# pidplate-mk-2.net
KiCad netlist of a schematic drawn in EAGLE
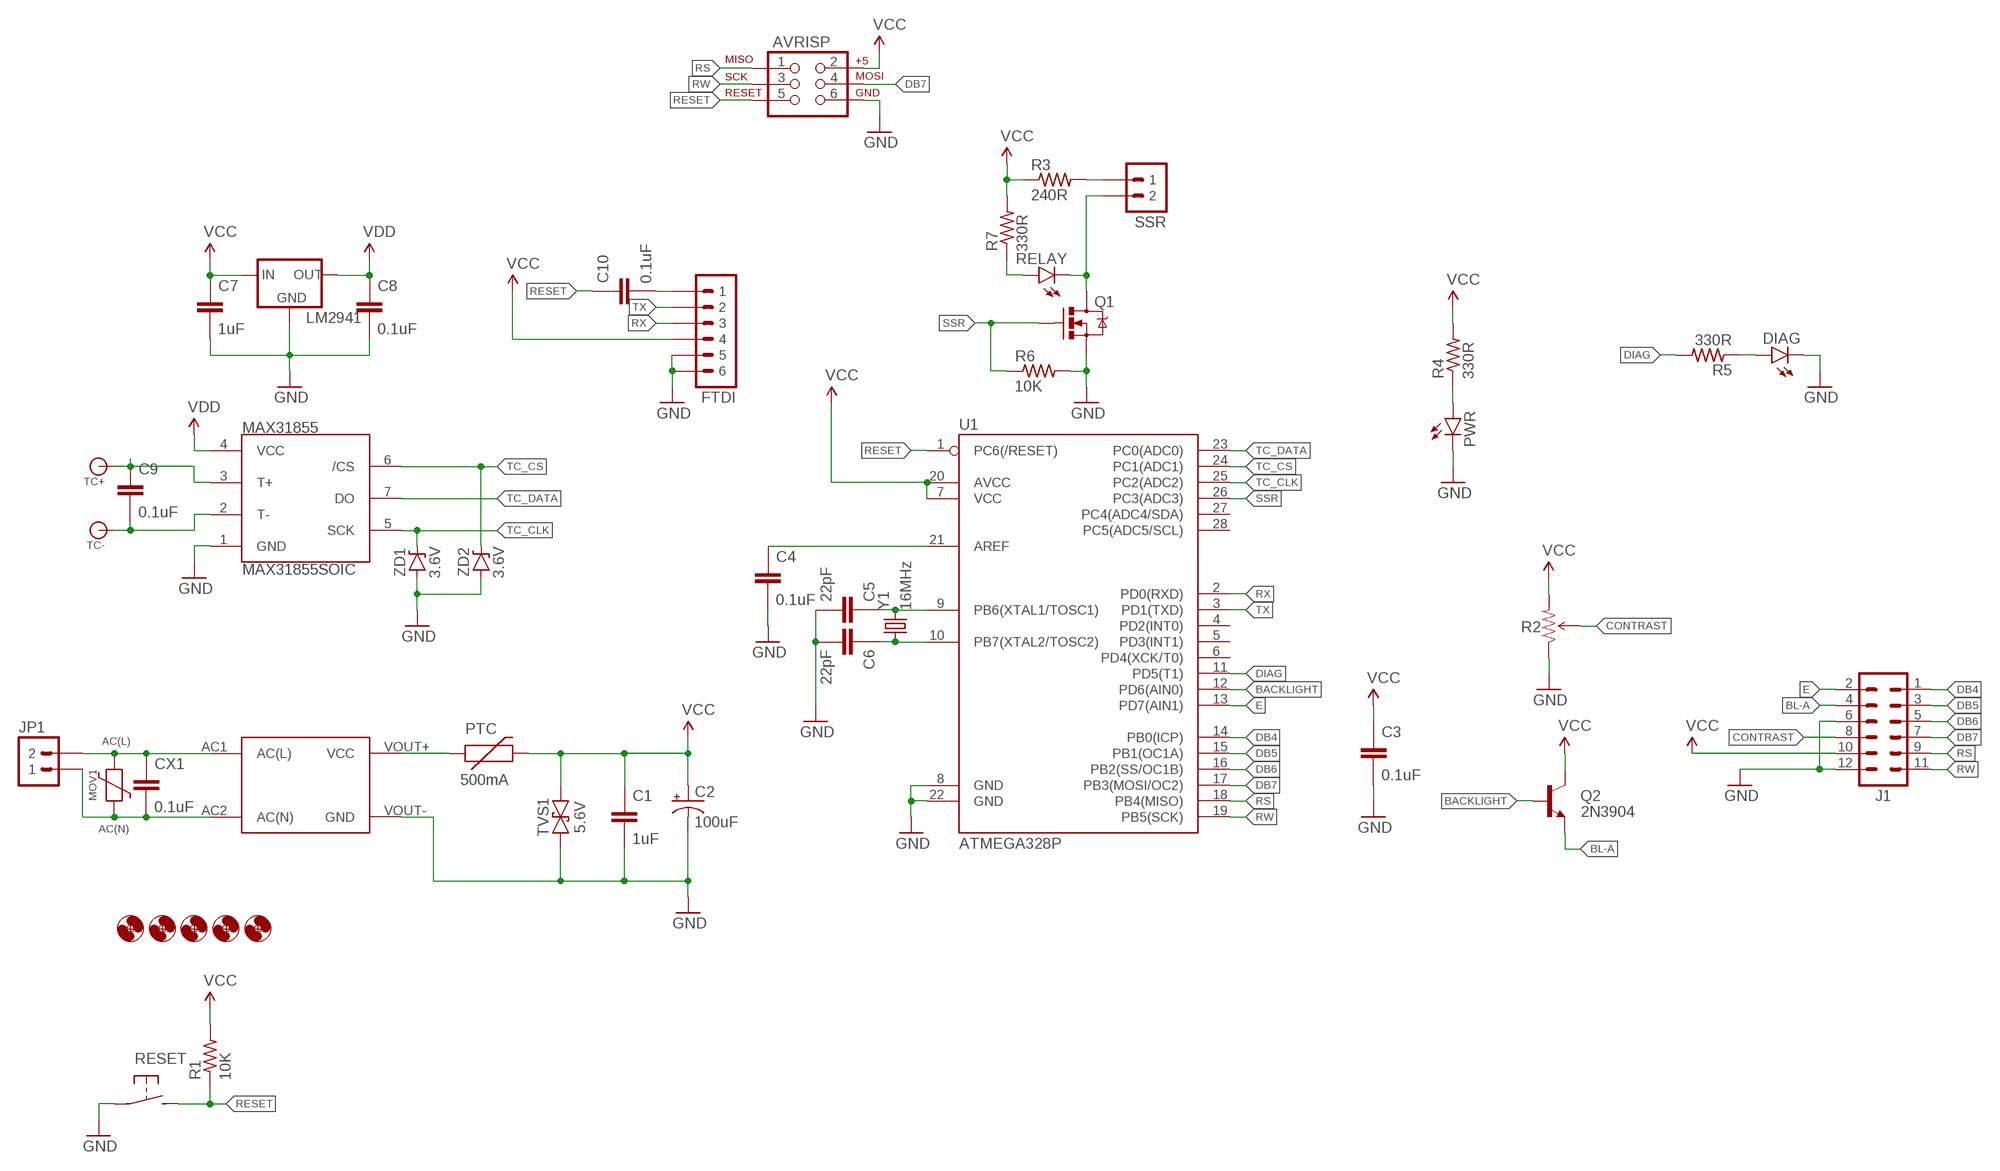
[diagram p0: schematic, sheet 1]

(export (version "E")
  (design (tool "Eeschema 10.0.6"))
  (components
    (comp (ref "AVRISP")
      (value "AVR_SPI_PRG_6PTH")
      (footprint "eagle-import:2X3")
      (libsource (lib "eagle-import") (part "AVR_SPI_PRG_6PTH"))
    )
    (comp (ref "C1")
      (value "1uF")
      (footprint "eagle-import:C025-024X044")
      (libsource (lib "eagle-import") (part "CAPACITOR-CERAMIC025-024X044"))
    )
    (comp (ref "C2")
      (value "100uF")
      (footprint "eagle-import:E2,5-7")
      (libsource (lib "eagle-import") (part "CAPACITOR-POLARIZEDE2.5-7"))
    )
    (comp (ref "C3")
      (value "0.1uF")
      (footprint "eagle-import:C025-024X044")
      (libsource (lib "eagle-import") (part "CAPACITOR-CERAMIC025-024X044"))
    )
    (comp (ref "C4")
      (value "0.1uF")
      (footprint "eagle-import:C025-024X044")
      (libsource (lib "eagle-import") (part "CAPACITOR-CERAMIC025-024X044"))
    )
    (comp (ref "C5")
      (value "22pF")
      (footprint "eagle-import:C025-024X044")
      (libsource (lib "eagle-import") (part "CAPACITOR-CERAMIC025-024X044"))
    )
    (comp (ref "C6")
      (value "22pF")
      (footprint "eagle-import:C025-024X044")
      (libsource (lib "eagle-import") (part "CAPACITOR-CERAMIC025-024X044"))
    )
    (comp (ref "C7")
      (value "1uF")
      (footprint "eagle-import:C025-024X044")
      (libsource (lib "eagle-import") (part "CAPACITOR-CERAMIC025-024X044"))
    )
    (comp (ref "C8")
      (value "0.1uF")
      (footprint "eagle-import:C025-024X044")
      (libsource (lib "eagle-import") (part "CAPACITOR-CERAMIC025-024X044"))
    )
    (comp (ref "C9")
      (value "0.1uF")
      (footprint "eagle-import:C025-024X044")
      (libsource (lib "eagle-import") (part "CAPACITOR-CERAMIC025-024X044"))
    )
    (comp (ref "C10")
      (value "0.1uF")
      (footprint "eagle-import:C025-024X044")
      (libsource (lib "eagle-import") (part "CAPACITOR-CERAMIC025-024X044"))
    )
    (comp (ref "CX1")
      (value "0.1uF")
      (footprint "eagle-import:XC10B5")
      (libsource (lib "eagle-import") (part "CXXC10B5"))
    )
    (comp (ref "DIAG")
      (value "LED3MM")
      (footprint "eagle-import:LED3MM")
      (libsource (lib "eagle-import") (part "LED3MM"))
    )
    (comp (ref "FTDI")
      (value "M06SIP")
      (footprint "eagle-import:1X06")
      (libsource (lib "eagle-import") (part "M06SIP"))
    )
    (comp (ref "H1")
      (value "HOLE#2")
      (footprint "eagle-import:HOLE-#2")
      (libsource (lib "eagle-import") (part "HOLE#2"))
    )
    (comp (ref "H2")
      (value "HOLE#2")
      (footprint "eagle-import:HOLE-#2")
      (libsource (lib "eagle-import") (part "HOLE#2"))
    )
    (comp (ref "H3")
      (value "HOLE#2")
      (footprint "eagle-import:HOLE-#2")
      (libsource (lib "eagle-import") (part "HOLE#2"))
    )
    (comp (ref "H4")
      (value "HOLE#2")
      (footprint "eagle-import:HOLE-#2")
      (libsource (lib "eagle-import") (part "HOLE#2"))
    )
    (comp (ref "H5")
      (value "HOLE#2")
      (footprint "eagle-import:HOLE-#2")
      (libsource (lib "eagle-import") (part "HOLE#2"))
    )
    (comp (ref "J1")
      (value "M06X2PTH")
      (footprint "eagle-import:2X6_PTH")
      (libsource (lib "eagle-import") (part "M06X2PTH"))
    )
    (comp (ref "JP1")
      (value "M023.5MM")
      (footprint "eagle-import:SCREWTERMINAL-3.5MM-2")
      (libsource (lib "eagle-import") (part "M023.5MM"))
    )
    (comp (ref "LM2941")
      (value "L2941")
      (footprint "eagle-import:TO-92-AMMO")
      (libsource (lib "eagle-import") (part "V_REG_78XXTO-92-INLINE"))
    )
    (comp (ref "MAX31855")
      (value "MAX31855SOIC")
      (footprint "eagle-import:SOIC127P600X175-8N")
      (libsource (lib "eagle-import") (part "MAX31855SOIC"))
    )
    (comp (ref "MOV1")
      (value "VARISITORVAR-5.08MM-PTH")
      (footprint "eagle-import:VAR-5.08MM-PTH")
      (libsource (lib "eagle-import") (part "VARISITORVAR-5.08MM-PTH"))
    )
    (comp (ref "PTC")
      (value "500mA")
      (footprint "eagle-import:PTC")
      (libsource (lib "eagle-import") (part "PTCPTH"))
    )
    (comp (ref "PWR")
      (value "LED3MM")
      (footprint "eagle-import:LED3MM")
      (libsource (lib "eagle-import") (part "LED3MM"))
    )
    (comp (ref "Q1")
      (value "2N7000")
      (footprint "eagle-import:TO-92-AMMO")
      (libsource (lib "eagle-import") (part "MOSFET-NCHANNEL2N7000-AMMO"))
    )
    (comp (ref "Q2")
      (value "2N3904")
      (footprint "eagle-import:TO-92-AMMO")
      (libsource (lib "eagle-import") (part "TRANSISTOR_NPNTO-92-AMMO-CBE"))
    )
    (comp (ref "R1")
      (value "10K")
      (footprint "eagle-import:RESISTOR-AXIAL-PTH-5.08MM")
      (libsource (lib "eagle-import") (part "RESISTORPTH-AXIAL-5.08MM"))
    )
    (comp (ref "R2")
      (value "20K")
      (footprint "eagle-import:TRIM_POT_PTH")
      (libsource (lib "eagle-import") (part "TRIMPOTPTH"))
    )
    (comp (ref "R3")
      (value "240R")
      (footprint "eagle-import:RESISTOR-AXIAL-PTH-6.35MM")
      (libsource (lib "eagle-import") (part "RESISTORPTH-AXIAL-6.35MM"))
    )
    (comp (ref "R4")
      (value "330R")
      (footprint "eagle-import:RESISTOR-AXIAL-PTH-5.08MM")
      (libsource (lib "eagle-import") (part "RESISTORPTH-AXIAL-5.08MM"))
    )
    (comp (ref "R5")
      (value "330R")
      (footprint "eagle-import:RESISTOR-AXIAL-PTH-5.08MM")
      (libsource (lib "eagle-import") (part "RESISTORPTH-AXIAL-5.08MM"))
    )
    (comp (ref "R6")
      (value "10K")
      (footprint "eagle-import:RESISTOR-AXIAL-PTH-6.35MM")
      (libsource (lib "eagle-import") (part "RESISTORPTH-AXIAL-6.35MM"))
    )
    (comp (ref "R7")
      (value "330R")
      (footprint "eagle-import:RESISTOR-AXIAL-PTH-5.08MM")
      (libsource (lib "eagle-import") (part "RESISTORPTH-AXIAL-5.08MM"))
    )
    (comp (ref "RELAY")
      (value "LED3MM")
      (footprint "eagle-import:LED3MM")
      (libsource (lib "eagle-import") (part "LED3MM"))
    )
    (comp (ref "RESET")
      (value "SPST-NO-TACT3MM-RA")
      (footprint "eagle-import:TACTILE-PTH-SIDE")
      (libsource (lib "eagle-import") (part "SPST-NO-TACT3MM-RA"))
    )
    (comp (ref "SSR")
      (value "M02JST-PTH-VERT")
      (footprint "eagle-import:JST-2-PH-VERT-PTH")
      (libsource (lib "eagle-import") (part "M02JST-PTH-VERT"))
    )
    (comp (ref "TC+")
      (value "BANANA_CONNPTH-RA")
      (footprint "eagle-import:BANANA-PTH-RA-SAFEWORD")
      (libsource (lib "eagle-import") (part "BANANA_CONNPTH-RA"))
    )
    (comp (ref "TC-")
      (value "BANANA_CONNPTH-RA")
      (footprint "eagle-import:BANANA-PTH-RA-SAFEWORD")
      (libsource (lib "eagle-import") (part "BANANA_CONNPTH-RA"))
    )
    (comp (ref "TVS1")
      (value "5.6V")
      (footprint "eagle-import:DO-41-TVS")
      (libsource (lib "eagle-import") (part "TVSDO-41-TVS-BIDIRECTIONAL"))
    )
    (comp (ref "U1")
      (value "ATMEGA328P")
      (footprint "eagle-import:DIL28-3")
      (libsource (lib "eagle-import") (part "ATMEGA328P_PDIP"))
    )
    (comp (ref "U3")
      (value "VSK-S1")
      (footprint "eagle-import:VSK-S1")
      (libsource (lib "eagle-import") (part "VSK-S1"))
    )
    (comp (ref "Y1")
      (value "16MHz")
      (footprint "eagle-import:HC49U-V")
      (libsource (lib "eagle-import") (part "CRYSTALHC49UV"))
    )
    (comp (ref "ZD1")
      (value "3.6V")
      (footprint "eagle-import:DIODE-7.68MM")
      (libsource (lib "eagle-import") (part "DIODE-ZENERPTH-7.68MM"))
    )
    (comp (ref "ZD2")
      (value "3.6V")
      (footprint "eagle-import:DIODE-7.68MM")
      (libsource (lib "eagle-import") (part "DIODE-ZENERPTH-7.68MM"))
    )
  )
  (nets
    (net (code "1") (name "/AC(L)") (class "Default")
      (node (ref "CX1") (pin "1") (pinfunction "1_1") (pintype "passive"))
      (node (ref "JP1") (pin "2") (pinfunction "2_2") (pintype "passive"))
      (node (ref "MOV1") (pin "2") (pinfunction "P$2_2") (pintype "bidirectional"))
      (node (ref "U3") (pin "AC1") (pinfunction "AC(L)_AC1") (pintype "bidirectional"))
    )
    (net (code "2") (name "/AC(N)") (class "Default")
      (node (ref "CX1") (pin "2") (pinfunction "2_2") (pintype "passive"))
      (node (ref "JP1") (pin "1") (pinfunction "1_1") (pintype "passive"))
      (node (ref "MOV1") (pin "1") (pinfunction "P$1_1") (pintype "bidirectional"))
      (node (ref "U3") (pin "AC2") (pinfunction "AC(N)_AC2") (pintype "bidirectional"))
    )
    (net (code "3") (name "BACKLIGHT") (class "Default")
      (node (ref "Q2") (pin "2") (pinfunction "B_2") (pintype "passive"))
      (node (ref "U1") (pin "12") (pinfunction "PD6(AIN0)_12") (pintype "bidirectional"))
    )
    (net (code "4") (name "BL-A") (class "Default")
      (node (ref "J1") (pin "4") (pinfunction "4_4") (pintype "passive"))
      (node (ref "Q2") (pin "3") (pinfunction "E_3") (pintype "passive"))
    )
    (net (code "5") (name "CONTRAST") (class "Default")
      (node (ref "J1") (pin "8") (pinfunction "8_8") (pintype "passive"))
      (node (ref "R2") (pin "2") (pinfunction "WIPER_2") (pintype "passive"))
    )
    (net (code "6") (name "DB4") (class "Default")
      (node (ref "J1") (pin "1") (pinfunction "1_1") (pintype "passive"))
      (node (ref "U1") (pin "14") (pinfunction "PB0(ICP)_14") (pintype "bidirectional"))
    )
    (net (code "7") (name "DB5") (class "Default")
      (node (ref "J1") (pin "3") (pinfunction "3_3") (pintype "passive"))
      (node (ref "U1") (pin "15") (pinfunction "PB1(OC1A)_15") (pintype "bidirectional"))
    )
    (net (code "8") (name "DB6") (class "Default")
      (node (ref "J1") (pin "5") (pinfunction "5_5") (pintype "passive"))
      (node (ref "U1") (pin "16") (pinfunction "PB2(SS/OC1B)_16") (pintype "bidirectional"))
    )
    (net (code "9") (name "DB7") (class "Default")
      (node (ref "AVRISP") (pin "4") (pinfunction "4_4") (pintype "passive"))
      (node (ref "J1") (pin "7") (pinfunction "7_7") (pintype "passive"))
      (node (ref "U1") (pin "17") (pinfunction "PB3(MOSI/OC2)_17") (pintype "bidirectional"))
    )
    (net (code "10") (name "DIAG") (class "Default")
      (node (ref "R5") (pin "P$2") (pinfunction "2_P$2") (pintype "passive"))
      (node (ref "U1") (pin "11") (pinfunction "PD5(T1)_11") (pintype "bidirectional"))
    )
    (net (code "11") (name "E") (class "Default")
      (node (ref "J1") (pin "2") (pinfunction "2_2") (pintype "passive"))
      (node (ref "U1") (pin "13") (pinfunction "PD7(AIN1)_13") (pintype "bidirectional"))
    )
    (net (code "12") (name "GND") (class "Default")
      (node (ref "AVRISP") (pin "6") (pinfunction "6_6") (pintype "passive"))
      (node (ref "C1") (pin "2") (pinfunction "2_2") (pintype "passive"))
      (node (ref "C2") (pin "-") (pinfunction "-_-") (pintype "passive"))
      (node (ref "C3") (pin "2") (pinfunction "2_2") (pintype "passive"))
      (node (ref "C4") (pin "2") (pinfunction "2_2") (pintype "passive"))
      (node (ref "C5") (pin "2") (pinfunction "2_2") (pintype "passive"))
      (node (ref "C6") (pin "2") (pinfunction "2_2") (pintype "passive"))
      (node (ref "C7") (pin "2") (pinfunction "2_2") (pintype "passive"))
      (node (ref "C8") (pin "2") (pinfunction "2_2") (pintype "passive"))
      (node (ref "DIAG") (pin "K") (pinfunction "C_K") (pintype "passive"))
      (node (ref "FTDI") (pin "5") (pinfunction "5_5") (pintype "passive"))
      (node (ref "FTDI") (pin "6") (pinfunction "6_6") (pintype "passive"))
      (node (ref "J1") (pin "12") (pinfunction "12_12") (pintype "passive"))
      (node (ref "J1") (pin "6") (pinfunction "6_6") (pintype "passive"))
      (node (ref "LM2941") (pin "2") (pinfunction "GND_2") (pintype "input"))
      (node (ref "MAX31855") (pin "1") (pinfunction "GND_1") (pintype "power_in"))
      (node (ref "PWR") (pin "K") (pinfunction "C_K") (pintype "passive"))
      (node (ref "Q1") (pin "1") (pinfunction "S_1") (pintype "passive"))
      (node (ref "R2") (pin "1") (pinfunction "CCW_1") (pintype "passive"))
      (node (ref "R6") (pin "P$2") (pinfunction "2_P$2") (pintype "passive"))
      (node (ref "RESET") (pin "1") (pinfunction "1_1") (pintype "passive"))
      (node (ref "TVS1") (pin "P$1") (pinfunction "1_P$1") (pintype "passive"))
      (node (ref "U1") (pin "22") (pinfunction "GND_22") (pintype "bidirectional"))
      (node (ref "U1") (pin "8") (pinfunction "GND_8") (pintype "bidirectional"))
      (node (ref "U3") (pin "VOUT-") (pinfunction "GND_VOUT-") (pintype "bidirectional"))
      (node (ref "ZD1") (pin "A") (pinfunction "A_A") (pintype "passive"))
      (node (ref "ZD2") (pin "A") (pinfunction "A_A") (pintype "passive"))
    )
    (net (code "13") (name "Net-(C10-Pad2)") (class "Default")
      (node (ref "C10") (pin "2") (pinfunction "2_2") (pintype "passive"))
      (node (ref "FTDI") (pin "1") (pinfunction "1_1") (pintype "passive"))
    )
    (net (code "14") (name "Net-(MAX31855-T+)") (class "Default")
      (node (ref "C9") (pin "1") (pinfunction "1_1") (pintype "passive"))
      (node (ref "MAX31855") (pin "3") (pinfunction "T+_3") (pintype "input"))
      (node (ref "TC+") (pin "P$1") (pinfunction "1_P$1") (pintype "passive"))
      (node (ref "TC+") (pin "P$2") (pinfunction "1_P$2") (pintype "passive"))
    )
    (net (code "15") (name "Net-(MAX31855-T-)") (class "Default")
      (node (ref "C9") (pin "2") (pinfunction "2_2") (pintype "passive"))
      (node (ref "MAX31855") (pin "2") (pinfunction "T-_2") (pintype "input"))
      (node (ref "TC-") (pin "P$1") (pinfunction "1_P$1") (pintype "passive"))
      (node (ref "TC-") (pin "P$2") (pinfunction "1_P$2") (pintype "passive"))
    )
    (net (code "16") (name "Net-(PTC-1)") (class "Default")
      (node (ref "PTC") (pin "P$1") (pinfunction "1_P$1") (pintype "bidirectional"))
      (node (ref "U3") (pin "VOUT+") (pinfunction "VCC_VOUT+") (pintype "bidirectional"))
    )
    (net (code "17") (name "Net-(Q1-D)") (class "Default")
      (node (ref "Q1") (pin "3") (pinfunction "D_3") (pintype "passive"))
      (node (ref "RELAY") (pin "K") (pinfunction "C_K") (pintype "passive"))
      (node (ref "SSR") (pin "2") (pinfunction "2_2") (pintype "passive"))
    )
    (net (code "18") (name "Net-(R3-2)") (class "Default")
      (node (ref "R3") (pin "P$2") (pinfunction "2_P$2") (pintype "passive"))
      (node (ref "SSR") (pin "1") (pinfunction "1_1") (pintype "passive"))
    )
    (net (code "19") (name "Net-(R4-1)") (class "Default")
      (node (ref "PWR") (pin "A") (pinfunction "A_A") (pintype "passive"))
      (node (ref "R4") (pin "P$1") (pinfunction "1_P$1") (pintype "passive"))
    )
    (net (code "20") (name "Net-(R5-1)") (class "Default")
      (node (ref "DIAG") (pin "A") (pinfunction "A_A") (pintype "passive"))
      (node (ref "R5") (pin "P$1") (pinfunction "1_P$1") (pintype "passive"))
    )
    (net (code "21") (name "Net-(R7-1)") (class "Default")
      (node (ref "R7") (pin "P$1") (pinfunction "1_P$1") (pintype "passive"))
      (node (ref "RELAY") (pin "A") (pinfunction "A_A") (pintype "passive"))
    )
    (net (code "22") (name "Net-(U1-AREF)") (class "Default")
      (node (ref "C4") (pin "1") (pinfunction "1_1") (pintype "passive"))
      (node (ref "U1") (pin "21") (pinfunction "AREF_21") (pintype "bidirectional"))
    )
    (net (code "23") (name "Net-(U1-PB6(XTAL1{slash}TOSC1))") (class "Default")
      (node (ref "C5") (pin "1") (pinfunction "1_1") (pintype "passive"))
      (node (ref "U1") (pin "9") (pinfunction "PB6(XTAL1/TOSC1)_9") (pintype "bidirectional"))
      (node (ref "Y1") (pin "2") (pinfunction "2_2") (pintype "passive"))
    )
    (net (code "24") (name "Net-(U1-PB7(XTAL2{slash}TOSC2))") (class "Default")
      (node (ref "C6") (pin "1") (pinfunction "1_1") (pintype "passive"))
      (node (ref "U1") (pin "10") (pinfunction "PB7(XTAL2/TOSC2)_10") (pintype "bidirectional"))
      (node (ref "Y1") (pin "1") (pinfunction "1_1") (pintype "passive"))
    )
    (net (code "25") (name "RESET") (class "Default")
      (node (ref "AVRISP") (pin "5") (pinfunction "5_5") (pintype "passive"))
      (node (ref "C10") (pin "1") (pinfunction "1_1") (pintype "passive"))
      (node (ref "R1") (pin "P$1") (pinfunction "1_P$1") (pintype "passive"))
      (node (ref "RESET") (pin "2") (pinfunction "2_2") (pintype "passive"))
      (node (ref "U1") (pin "1") (pinfunction "PC6(/RESET)_1") (pintype "bidirectional"))
    )
    (net (code "26") (name "RS") (class "Default")
      (node (ref "AVRISP") (pin "1") (pinfunction "1_1") (pintype "passive"))
      (node (ref "J1") (pin "9") (pinfunction "9_9") (pintype "passive"))
      (node (ref "U1") (pin "18") (pinfunction "PB4(MISO)_18") (pintype "bidirectional"))
    )
    (net (code "27") (name "RW") (class "Default")
      (node (ref "AVRISP") (pin "3") (pinfunction "3_3") (pintype "passive"))
      (node (ref "J1") (pin "11") (pinfunction "11_11") (pintype "passive"))
      (node (ref "U1") (pin "19") (pinfunction "PB5(SCK)_19") (pintype "bidirectional"))
    )
    (net (code "28") (name "RX") (class "Default")
      (node (ref "FTDI") (pin "3") (pinfunction "3_3") (pintype "passive"))
      (node (ref "U1") (pin "2") (pinfunction "PD0(RXD)_2") (pintype "bidirectional"))
    )
    (net (code "29") (name "SSR") (class "Default")
      (node (ref "Q1") (pin "2") (pinfunction "G_2") (pintype "passive"))
      (node (ref "R6") (pin "P$1") (pinfunction "1_P$1") (pintype "passive"))
      (node (ref "U1") (pin "26") (pinfunction "PC3(ADC3)_26") (pintype "bidirectional"))
    )
    (net (code "30") (name "TC_CLK") (class "Default")
      (node (ref "MAX31855") (pin "5") (pinfunction "SCK_5") (pintype "input"))
      (node (ref "U1") (pin "25") (pinfunction "PC2(ADC2)_25") (pintype "bidirectional"))
      (node (ref "ZD1") (pin "K") (pinfunction "C_K") (pintype "passive"))
    )
    (net (code "31") (name "TC_CS") (class "Default")
      (node (ref "MAX31855") (pin "6") (pinfunction "/CS_6") (pintype "input"))
      (node (ref "U1") (pin "24") (pinfunction "PC1(ADC1)_24") (pintype "bidirectional"))
      (node (ref "ZD2") (pin "K") (pinfunction "C_K") (pintype "passive"))
    )
    (net (code "32") (name "TC_DATA") (class "Default")
      (node (ref "MAX31855") (pin "7") (pinfunction "DO_7") (pintype "output"))
      (node (ref "U1") (pin "23") (pinfunction "PC0(ADC0)_23") (pintype "bidirectional"))
    )
    (net (code "33") (name "TX") (class "Default")
      (node (ref "FTDI") (pin "2") (pinfunction "2_2") (pintype "passive"))
      (node (ref "U1") (pin "3") (pinfunction "PD1(TXD)_3") (pintype "bidirectional"))
    )
    (net (code "34") (name "VCC") (class "Default")
      (node (ref "AVRISP") (pin "2") (pinfunction "2_2") (pintype "passive"))
      (node (ref "C1") (pin "1") (pinfunction "1_1") (pintype "passive"))
      (node (ref "C2") (pin "+") (pinfunction "+_+") (pintype "passive"))
      (node (ref "C3") (pin "1") (pinfunction "1_1") (pintype "passive"))
      (node (ref "C7") (pin "1") (pinfunction "1_1") (pintype "passive"))
      (node (ref "FTDI") (pin "4") (pinfunction "4_4") (pintype "passive"))
      (node (ref "J1") (pin "10") (pinfunction "10_10") (pintype "passive"))
      (node (ref "LM2941") (pin "1") (pinfunction "IN_1") (pintype "input"))
      (node (ref "PTC") (pin "P$2") (pinfunction "2_P$2") (pintype "bidirectional"))
      (node (ref "Q2") (pin "1") (pinfunction "C_1") (pintype "passive"))
      (node (ref "R1") (pin "P$2") (pinfunction "2_P$2") (pintype "passive"))
      (node (ref "R2") (pin "3") (pinfunction "CW_3") (pintype "passive"))
      (node (ref "R3") (pin "P$1") (pinfunction "1_P$1") (pintype "passive"))
      (node (ref "R4") (pin "P$2") (pinfunction "2_P$2") (pintype "passive"))
      (node (ref "R7") (pin "P$2") (pinfunction "2_P$2") (pintype "passive"))
      (node (ref "TVS1") (pin "P$2") (pinfunction "2_P$2") (pintype "passive"))
      (node (ref "U1") (pin "20") (pinfunction "AVCC_20") (pintype "bidirectional"))
      (node (ref "U1") (pin "7") (pinfunction "VCC_7") (pintype "bidirectional"))
    )
    (net (code "35") (name "VDD") (class "Default")
      (node (ref "C8") (pin "1") (pinfunction "1_1") (pintype "passive"))
      (node (ref "LM2941") (pin "3") (pinfunction "OUT_3") (pintype "output"))
      (node (ref "MAX31855") (pin "4") (pinfunction "VCC_4") (pintype "power_in"))
    )
    (net (code "36") (name "unconnected-(U1-PC4(ADC4{slash}SDA)-Pad27)") (class "Default")
      (node (ref "U1") (pin "27") (pinfunction "PC4(ADC4/SDA)_27") (pintype "bidirectional"))
    )
    (net (code "37") (name "unconnected-(U1-PC5(ADC5{slash}SCL)-Pad28)") (class "Default")
      (node (ref "U1") (pin "28") (pinfunction "PC5(ADC5/SCL)_28") (pintype "bidirectional"))
    )
    (net (code "38") (name "unconnected-(U1-PD2(INT0)-Pad4)") (class "Default")
      (node (ref "U1") (pin "4") (pinfunction "PD2(INT0)_4") (pintype "bidirectional"))
    )
    (net (code "39") (name "unconnected-(U1-PD3(INT1)-Pad5)") (class "Default")
      (node (ref "U1") (pin "5") (pinfunction "PD3(INT1)_5") (pintype "bidirectional"))
    )
    (net (code "40") (name "unconnected-(U1-PD4(XCK{slash}T0)-Pad6)") (class "Default")
      (node (ref "U1") (pin "6") (pinfunction "PD4(XCK/T0)_6") (pintype "bidirectional"))
    )
  )
)
